# FMC_EEPROM.net
KiCad netlist of a schematic drawn in Altium Designer
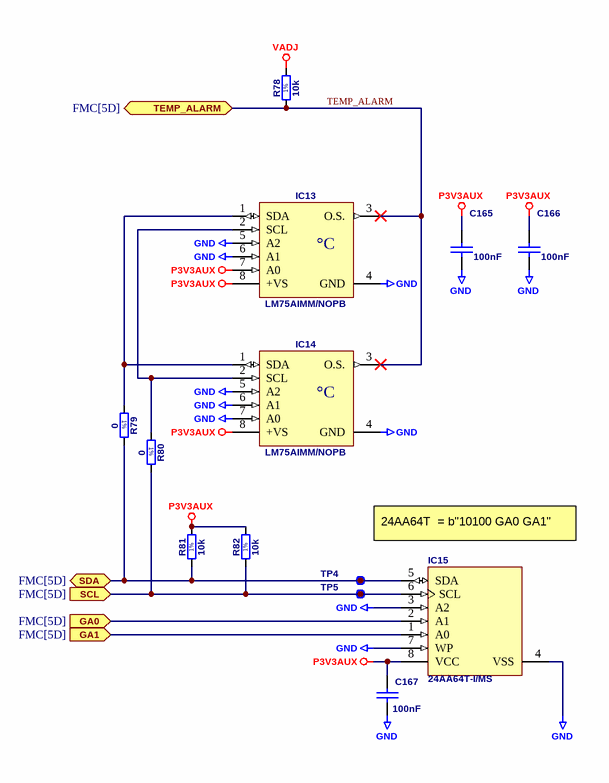
[diagram p0: FMC_EEPROM.SchDoc]

(export (version "E")
  (design (tool "Eeschema 10.0.6"))
  (components
    (comp (ref "C165")
      (value "100nF")
      (footprint "CAPC0603X33N")
      (description "Non-polarised capacitor")
      (fields
        (field (name "PART NUMBER") "CC0201_100NF_6.3V_10%_X5R")
        (field (name "VOLTAGE") "6.3V")
        (field (name "AUTHOR") "CERN DEM JLC")
      )
      (libsource (lib "Capacitors") (part "Capacitor - non polarized"))
    )
    (comp (ref "C166")
      (value "100nF")
      (footprint "CAPC0603X33N")
      (description "Non-polarised capacitor")
      (fields
        (field (name "PART NUMBER") "CC0201_100NF_6.3V_10%_X5R")
        (field (name "VOLTAGE") "6.3V")
        (field (name "AUTHOR") "CERN DEM JLC")
      )
      (libsource (lib "Capacitors") (part "Capacitor - non polarized"))
    )
    (comp (ref "C167")
      (value "100nF")
      (footprint "CAPC0603X33N")
      (description "Non-polarised capacitor")
      (fields
        (field (name "PART NUMBER") "CC0201_100NF_6.3V_10%_X5R")
        (field (name "VOLTAGE") "6.3V")
        (field (name "AUTHOR") "CERN DEM JLC")
      )
      (libsource (lib "Capacitors") (part "Capacitor - non polarized"))
    )
    (comp (ref "IC13")
      (value "LM75AIMM/NOPB")
      (footprint "SOP65P490X109-8N")
      (description "Digital Temperature Sensor and Thermal Watchdog with Two-Wire Interface")
      (fields (field (name "MANUFACTURER") "TEXAS INSTRUMENTS") (field (name "AUTHOR") "CERN DEM JLC"))
      (libsource (lib "ICs And Semiconductors") (part "LM75"))
    )
    (comp (ref "IC14")
      (value "LM75AIMM/NOPB")
      (footprint "SOP65P490X109-8N")
      (description "Digital Temperature Sensor and Thermal Watchdog with Two-Wire Interface")
      (fields (field (name "MANUFACTURER") "TEXAS INSTRUMENTS") (field (name "AUTHOR") "CERN DEM JLC"))
      (libsource (lib "ICs And Semiconductors") (part "LM75"))
    )
    (comp (ref "IC15")
      (value "24AA64T-I/MS")
      (footprint "SOP65P490X110-8N")
      (description "1.7V-5.5V, 64K  (8K x 8-bit) I2C Serial EEPROM")
      (fields (field (name "MANUFACTURER") "MICROCHIP TECHNOLOGY") (field (name "AUTHOR") "CERN DEM JMW"))
      (libsource (lib "ICs And Semiconductors") (part "24AA64T-I/MS"))
    )
    (comp (ref "R78")
      (value "10k")
      (footprint "RESC1005X40N")
      (description "Resistor - 1%")
      (fields
        (field (name "PART NUMBER") "R0402_10K_1%_0.0625W_100PPM")
        (field (name "POWER") "0.0625W")
        (field (name "AUTHOR") "CERN DEM JLC")
      )
      (libsource (lib "Resistors") (part "Resistor - 1%"))
    )
    (comp (ref "R79")
      (value "0")
      (footprint "RESC1005X40N")
      (description "Resistor - 1%")
      (fields
        (field (name "PART NUMBER") "R0402_0R_JUMPER")
        (field (name "MANUFACTURER") "GENERIC")
        (field (name "AUTHOR") "CERN DEM JLC")
      )
      (libsource (lib "Resistors") (part "Resistor - 1%"))
    )
    (comp (ref "R80")
      (value "0")
      (footprint "RESC1005X40N")
      (description "Resistor - 1%")
      (fields
        (field (name "PART NUMBER") "R0402_0R_JUMPER")
        (field (name "MANUFACTURER") "GENERIC")
        (field (name "AUTHOR") "CERN DEM JLC")
      )
      (libsource (lib "Resistors") (part "Resistor - 1%"))
    )
    (comp (ref "R81")
      (value "10k")
      (footprint "RESC1005X40N")
      (description "Resistor - 1%")
      (fields
        (field (name "PART NUMBER") "R0402_10K_1%_0.0625W_100PPM")
        (field (name "POWER") "0.0625W")
        (field (name "AUTHOR") "CERN DEM JLC")
      )
      (libsource (lib "Resistors") (part "Resistor - 1%"))
    )
    (comp (ref "R82")
      (value "10k")
      (footprint "RESC1005X40N")
      (description "Resistor - 1%")
      (fields
        (field (name "PART NUMBER") "R0402_10K_1%_0.0625W_100PPM")
        (field (name "POWER") "0.0625W")
        (field (name "AUTHOR") "CERN DEM JLC")
      )
      (libsource (lib "Resistors") (part "Resistor - 1%"))
    )
    (comp (ref "TP4")
      (value "SMD Pad")
      (footprint "C100")
      (description "Through Hole Pad")
      (fields (field (name "PART NUMBER") "SMD_PAD_D1MM") (field (name "AUTHOR") "CERN DEM JLC"))
      (libsource (lib "Eletro-mechanical") (part "Single SMD Pad (Round)"))
    )
    (comp (ref "TP5")
      (value "SMD Pad")
      (footprint "C100")
      (description "Through Hole Pad")
      (fields (field (name "PART NUMBER") "SMD_PAD_D1MM") (field (name "AUTHOR") "CERN DEM JLC"))
      (libsource (lib "Eletro-mechanical") (part "Single SMD Pad (Round)"))
    )
  )
  (nets
    (net (code "1") (name "/GA0") (class "Default")
      (node (ref "IC15") (pin "2") (pinfunction "A1_2") (pintype "input"))
    )
    (net (code "2") (name "/GA1") (class "Default")
      (node (ref "IC15") (pin "1") (pinfunction "A0_1") (pintype "input"))
    )
    (net (code "3") (name "/SCL") (class "Default")
      (node (ref "IC15") (pin "6") (pinfunction "SCL_6") (pintype "input"))
      (node (ref "R80") (pin "2") (pinfunction "2_2") (pintype "passive"))
      (node (ref "R82") (pin "1") (pinfunction "1_1") (pintype "passive"))
      (node (ref "TP5") (pin "1") (pinfunction "1_1") (pintype "bidirectional"))
    )
    (net (code "4") (name "/SDA") (class "Default")
      (node (ref "IC15") (pin "5") (pinfunction "SDA_5") (pintype "bidirectional"))
      (node (ref "R79") (pin "2") (pinfunction "2_2") (pintype "passive"))
      (node (ref "R81") (pin "1") (pinfunction "1_1") (pintype "passive"))
      (node (ref "TP4") (pin "1") (pinfunction "1_1") (pintype "bidirectional"))
    )
    (net (code "5") (name "/TEMP_ALARM") (class "Default")
      (node (ref "IC13") (pin "3") (pinfunction "O.S._3") (pintype "output"))
      (node (ref "IC14") (pin "3") (pinfunction "O.S._3") (pintype "output"))
      (node (ref "R78") (pin "1") (pinfunction "1_1") (pintype "passive"))
    )
    (net (code "6") (name "GND") (class "Default")
      (node (ref "C165") (pin "2") (pinfunction "2_2") (pintype "passive"))
      (node (ref "C166") (pin "2") (pinfunction "2_2") (pintype "passive"))
      (node (ref "C167") (pin "2") (pinfunction "2_2") (pintype "passive"))
      (node (ref "IC13") (pin "4") (pinfunction "GND_4") (pintype "power_in"))
      (node (ref "IC13") (pin "5") (pinfunction "A2_5") (pintype "input"))
      (node (ref "IC13") (pin "6") (pinfunction "A1_6") (pintype "input"))
      (node (ref "IC14") (pin "4") (pinfunction "GND_4") (pintype "power_in"))
      (node (ref "IC14") (pin "5") (pinfunction "A2_5") (pintype "input"))
      (node (ref "IC14") (pin "6") (pinfunction "A1_6") (pintype "input"))
      (node (ref "IC14") (pin "7") (pinfunction "A0_7") (pintype "input"))
      (node (ref "IC15") (pin "3") (pinfunction "A2_3") (pintype "input"))
      (node (ref "IC15") (pin "4") (pinfunction "VSS_4") (pintype "power_in"))
      (node (ref "IC15") (pin "7") (pinfunction "WP_7") (pintype "input"))
    )
    (net (code "7") (name "Net-(IC13-SCL)") (class "Default")
      (node (ref "IC13") (pin "2") (pinfunction "SCL_2") (pintype "input"))
      (node (ref "IC14") (pin "2") (pinfunction "SCL_2") (pintype "input"))
      (node (ref "R80") (pin "1") (pinfunction "1_1") (pintype "passive"))
    )
    (net (code "8") (name "Net-(IC13-SDA)") (class "Default")
      (node (ref "IC13") (pin "1") (pinfunction "SDA_1") (pintype "bidirectional"))
      (node (ref "IC14") (pin "1") (pinfunction "SDA_1") (pintype "bidirectional"))
      (node (ref "R79") (pin "1") (pinfunction "1_1") (pintype "passive"))
    )
    (net (code "9") (name "P3V3AUX") (class "Default")
      (node (ref "C165") (pin "1") (pinfunction "1_1") (pintype "passive"))
      (node (ref "C166") (pin "1") (pinfunction "1_1") (pintype "passive"))
      (node (ref "C167") (pin "1") (pinfunction "1_1") (pintype "passive"))
      (node (ref "IC13") (pin "7") (pinfunction "A0_7") (pintype "input"))
      (node (ref "IC13") (pin "8") (pinfunction "+VS_8") (pintype "power_in"))
      (node (ref "IC14") (pin "8") (pinfunction "+VS_8") (pintype "power_in"))
      (node (ref "IC15") (pin "8") (pinfunction "VCC_8") (pintype "power_in"))
      (node (ref "R81") (pin "2") (pinfunction "2_2") (pintype "passive"))
      (node (ref "R82") (pin "2") (pinfunction "2_2") (pintype "passive"))
    )
    (net (code "10") (name "VADJ") (class "Default")
      (node (ref "R78") (pin "2") (pinfunction "2_2") (pintype "passive"))
    )
  )
)
